# BlockDetector.net
KiCad netlist of a schematic drawn in Altium Designer
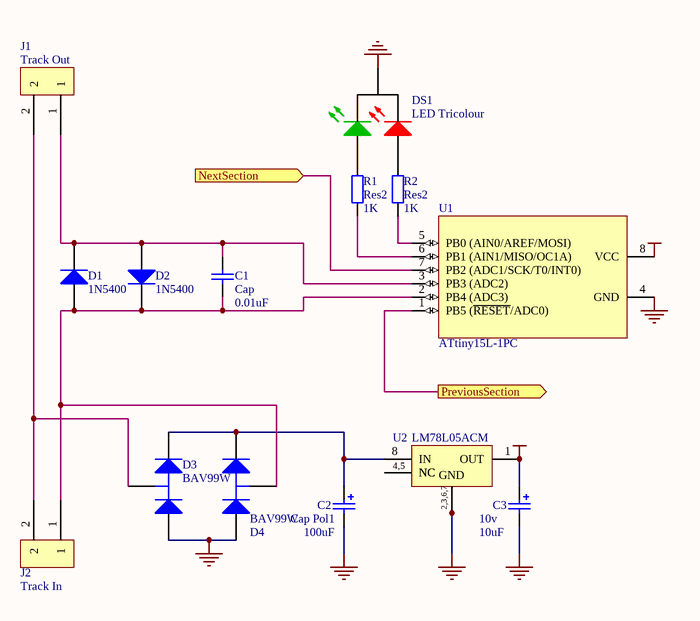
[diagram p0: BlockDetector.SchDoc]

(export (version "E")
  (design (tool "Eeschema 10.0.6"))
  (components
    (comp (ref "C1")
      (value "Cap")
      (footprint "RAD-0.3")
      (description "Capacitor")
      (fields (field (name "ALTIUM_VALUE") "0.01uF") (field (name "PUBLISHER") "Altium Limited"))
      (libsource (lib "Miscellaneous Devices") (part "Cap"))
    )
    (comp (ref "C2")
      (value "Cap Pol1")
      (footprint "CAPPR5-10X10.5")
      (description "Polarized Capacitor (Radial)")
      (fields (field (name "ALTIUM_VALUE") "100uF") (field (name "PUBLISHER") "Altium Limited"))
      (libsource (lib "Miscellaneous Devices") (part "Cap Pol1"))
    )
    (comp (ref "C3")
      (value "10v")
      (footprint "CC3216-1206")
      (description "Polarized Capacitor (Radial)")
      (fields (field (name "ALTIUM_VALUE") "10uF") (field (name "PUBLISHER") "Altium Limited"))
      (libsource (lib "Miscellaneous Devices") (part "Cap Pol1"))
    )
    (comp (ref "D1")
      (value "1N5400")
      (footprint "DIO18.84-9.6x5.6")
      (description "3 Amp General Purpose Rectifier")
      (fields (field (name "PUBLISHER") "Altium Limited"))
      (libsource (lib "Miscellaneous Devices") (part "Diode 1N5400"))
    )
    (comp (ref "D2")
      (value "1N5400")
      (footprint "DIO18.84-9.6x5.6")
      (description "3 Amp General Purpose Rectifier")
      (fields (field (name "PUBLISHER") "Altium Limited"))
      (libsource (lib "Miscellaneous Devices") (part "Diode 1N5400"))
    )
    (comp (ref "D3")
      (value "BAV99W")
      (footprint "SOT-323")
      (description "Silicon Switching Diode Array for High-Speed Switching")
      (fields (field (name "PUBLISHER") "Altium Limited"))
      (libsource (lib "Infineon Discrete Diode") (part "BAV99W"))
    )
    (comp (ref "D4")
      (value "BAV99W")
      (footprint "SOT-323")
      (description "Silicon Switching Diode Array for High-Speed Switching")
      (fields (field (name "PUBLISHER") "Altium Limited"))
      (libsource (lib "Infineon Discrete Diode") (part "BAV99W"))
    )
    (comp (ref "DS1")
      (value "LED Tricolour")
      (footprint "LED5mm TriColour")
      (description "Typical Red Green Tri Color LED")
      (fields (field (name "PUBLISHER") "Altium Limited"))
      (libsource (lib "Custom") (part "LED Tricolour"))
    )
    (comp (ref "J1")
      (value "Track Out")
      (footprint "0.156 SIP 2 PIN")
      (libsource (lib "Custom") (part "SIP2 CONNECTOR"))
    )
    (comp (ref "J2")
      (value "Track In")
      (footprint "0.156 SIP 2 PIN")
      (libsource (lib "") (part "SIP2 CONNECTOR_1"))
    )
    (comp (ref "R1")
      (value "Res2")
      (footprint "AXIAL-0.4")
      (description "Resistor")
      (fields (field (name "ALTIUM_VALUE") "1K") (field (name "PUBLISHER") "Altium Limited"))
      (libsource (lib "Miscellaneous Devices") (part "Res2"))
    )
    (comp (ref "R2")
      (value "Res2")
      (footprint "AXIAL-0.4")
      (description "Resistor")
      (fields (field (name "ALTIUM_VALUE") "1K") (field (name "PUBLISHER") "Altium Limited"))
      (libsource (lib "Miscellaneous Devices") (part "Res2"))
    )
    (comp (ref "U1")
      (value "ATtiny15L-1PC")
      (footprint "8P3")
      (description "8-Bit AVR Microcontroller with 1K Byte of Flash Memory")
      (fields (field (name "PUBLISHER") "Altium Limited"))
      (libsource (lib "Atmel Microcontroller 8-Bit AVR") (part "ATtiny15L-1PC"))
    )
    (comp (ref "U2")
      (value "LM78L05ACM")
      (footprint "M08A")
      (description "3-Terminal Positive Regulator")
      (fields (field (name "PUBLISHER") "Altium Limited"))
      (libsource (lib "NSC Power Mgt Voltage Regulator") (part "LM78L05ACM"))
    )
  )
  (nets
    (net (code "1") (name "/NextSection") (class "Default")
      (node (ref "U1") (pin "7") (pinfunction "PB2_(ADC1/SCK/T0/INT0)_7") (pintype "bidirectional"))
    )
    (net (code "2") (name "/PreviousSection") (class "Default")
      (node (ref "U1") (pin "1") (pinfunction "PB5_(~{RESET}/ADC0)_1") (pintype "bidirectional"))
    )
    (net (code "3") (name "GND") (class "Default")
      (node (ref "C2") (pin "2") (pinfunction "2_2") (pintype "passive"))
      (node (ref "C3") (pin "2") (pinfunction "2_2") (pintype "passive"))
      (node (ref "D3") (pin "1") (pinfunction "A_1") (pintype "passive"))
      (node (ref "D4") (pin "1") (pinfunction "A_1") (pintype "passive"))
      (node (ref "DS1") (pin "2") (pinfunction "K_2") (pintype "passive"))
      (node (ref "U1") (pin "4") (pinfunction "GND_4") (pintype "power_in"))
      (node (ref "U2") (pin "2") (pinfunction "GND_2") (pintype "power_in"))
      (node (ref "U2") (pin "3") (pinfunction "GND_3") (pintype "power_in"))
      (node (ref "U2") (pin "6") (pinfunction "GND_6") (pintype "power_in"))
      (node (ref "U2") (pin "7") (pinfunction "GND_7") (pintype "power_in"))
    )
    (net (code "4") (name "Net-(D1-A)") (class "Default")
      (node (ref "C1") (pin "1") (pinfunction "1_1") (pintype "passive"))
      (node (ref "D1") (pin "1") (pinfunction "A_1") (pintype "passive"))
      (node (ref "D2") (pin "2") (pinfunction "K_2") (pintype "passive"))
      (node (ref "D4") (pin "3") (pinfunction "C_3") (pintype "passive"))
      (node (ref "J2") (pin "1") (pinfunction "1_1") (pintype "passive"))
      (node (ref "U1") (pin "2") (pinfunction "PB4_(ADC3)_2") (pintype "bidirectional"))
    )
    (net (code "5") (name "Net-(D1-K)") (class "Default")
      (node (ref "C1") (pin "2") (pinfunction "2_2") (pintype "passive"))
      (node (ref "D1") (pin "2") (pinfunction "K_2") (pintype "passive"))
      (node (ref "D2") (pin "1") (pinfunction "A_1") (pintype "passive"))
      (node (ref "J1") (pin "1") (pinfunction "1_1") (pintype "passive"))
      (node (ref "U1") (pin "3") (pinfunction "PB3_(ADC2)_3") (pintype "bidirectional"))
    )
    (net (code "6") (name "Net-(D3-C)") (class "Default")
      (node (ref "D3") (pin "3") (pinfunction "C_3") (pintype "passive"))
      (node (ref "J1") (pin "2") (pinfunction "2_2") (pintype "passive"))
      (node (ref "J2") (pin "2") (pinfunction "2_2") (pintype "passive"))
    )
    (net (code "7") (name "Net-(D3-K)") (class "Default")
      (node (ref "C2") (pin "1") (pinfunction "1_1") (pintype "passive"))
      (node (ref "D3") (pin "2") (pinfunction "K_2") (pintype "passive"))
      (node (ref "D4") (pin "2") (pinfunction "K_2") (pintype "passive"))
      (node (ref "U2") (pin "8") (pinfunction "IN_8") (pintype "power_in"))
    )
    (net (code "8") (name "Net-(DS1-Ag)") (class "Default")
      (node (ref "DS1") (pin "1") (pinfunction "Ag_1") (pintype "passive"))
      (node (ref "R1") (pin "2") (pinfunction "2_2") (pintype "passive"))
    )
    (net (code "9") (name "Net-(DS1-Ar)") (class "Default")
      (node (ref "DS1") (pin "3") (pinfunction "Ar_3") (pintype "passive"))
      (node (ref "R2") (pin "2") (pinfunction "2_2") (pintype "passive"))
    )
    (net (code "10") (name "Net-(U1-PB0_(AIN0{slash}AREF{slash}MOSI))") (class "Default")
      (node (ref "R2") (pin "1") (pinfunction "1_1") (pintype "passive"))
      (node (ref "U1") (pin "5") (pinfunction "PB0_(AIN0/AREF/MOSI)_5") (pintype "bidirectional"))
    )
    (net (code "11") (name "Net-(U1-PB1_(AIN1{slash}MISO{slash}OC1A))") (class "Default")
      (node (ref "R1") (pin "1") (pinfunction "1_1") (pintype "passive"))
      (node (ref "U1") (pin "6") (pinfunction "PB1_(AIN1/MISO/OC1A)_6") (pintype "bidirectional"))
    )
    (net (code "12") (name "Net-(U2-NC-Pad4)") (class "Default")
      (node (ref "U2") (pin "4") (pinfunction "NC_4") (pintype "passive"))
      (node (ref "U2") (pin "5") (pinfunction "NC_5") (pintype "passive"))
    )
    (net (code "13") (name "VCC") (class "Default")
      (node (ref "C3") (pin "1") (pinfunction "1_1") (pintype "passive"))
      (node (ref "U1") (pin "8") (pinfunction "VCC_8") (pintype "power_in"))
      (node (ref "U2") (pin "1") (pinfunction "OUT_1") (pintype "power_in"))
    )
  )
)
